# Z05_MB_01.net
KiCad netlist of a schematic drawn in EAGLE
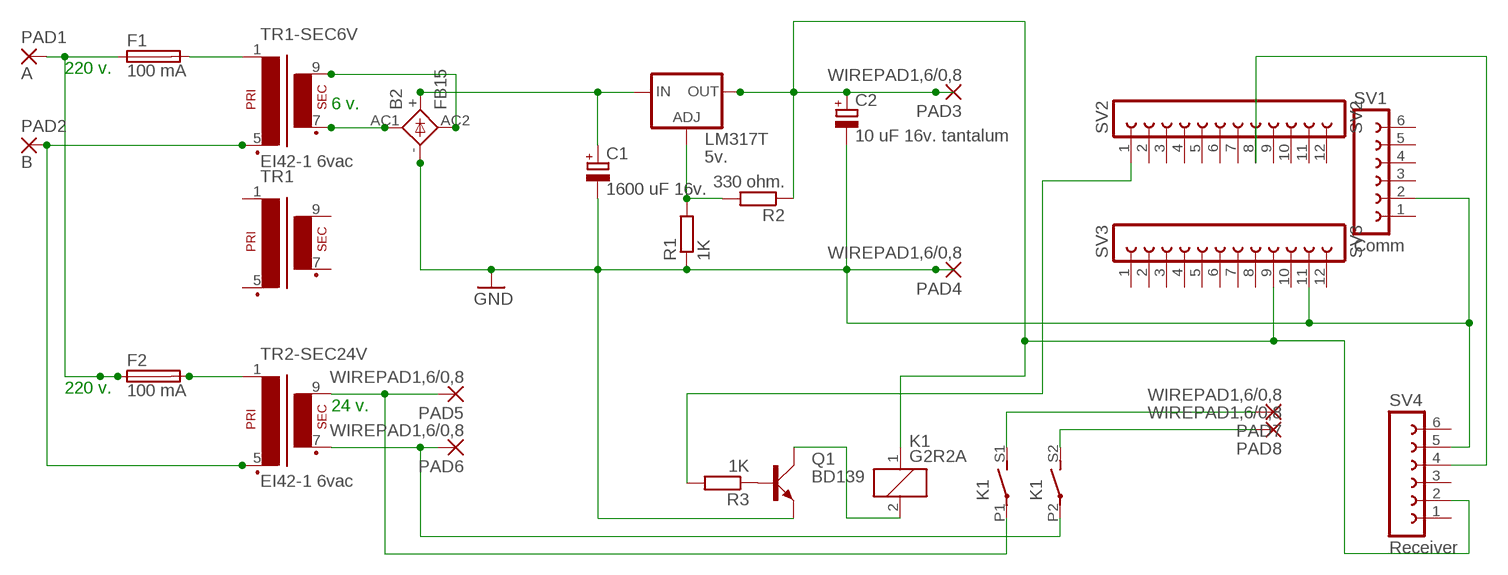
[diagram p0: schematic, sheet 1]

(export (version "E")
  (design (tool "Eeschema 10.0.6"))
  (components
    (comp (ref "B2")
      (value "FB15")
      (footprint "eagle-import:FB15")
      (libsource (lib "eagle-import") (part "FB15"))
    )
    (comp (ref "C1")
      (value "1600 uF 16v.")
      (footprint "eagle-import:E5-13")
      (libsource (lib "eagle-import") (part "CPOL-EUE5-13"))
    )
    (comp (ref "C2")
      (value "10 uF 16v. tantalum")
      (footprint "eagle-import:TAP5-60")
      (libsource (lib "eagle-import") (part "CPOL-EUTAP5-60"))
    )
    (comp (ref "F1")
      (value "100 mA")
      (footprint "eagle-import:GSH15")
      (fields (field (name "MPN") "64900001039"))
      (libsource (lib "eagle-import") (part "GSH15"))
    )
    (comp (ref "F2")
      (value "100 mA")
      (footprint "eagle-import:GSH15")
      (fields (field (name "MPN") "64900001039"))
      (libsource (lib "eagle-import") (part "GSH15"))
    )
    (comp (ref "K1")
      (value "G2R2A")
      (footprint "eagle-import:G2R2A")
      (fields (field (name "MPN") "G2R-2A-DC24"))
      (libsource (lib "eagle-import") (part "G2R2A"))
    )
    (comp (ref "LM317T")
      (value "5v.")
      (footprint "eagle-import:317TS")
      (libsource (lib "eagle-import") (part "LM317TS"))
    )
    (comp (ref "PAD1")
      (value "A")
      (footprint "eagle-import:2,54_1,1")
      (libsource (lib "eagle-import") (part "2,54/1,1"))
    )
    (comp (ref "PAD2")
      (value "B")
      (footprint "eagle-import:2,54_1,1")
      (libsource (lib "eagle-import") (part "2,54/1,1"))
    )
    (comp (ref "PAD3")
      (value "WIREPAD1,6/0,8")
      (footprint "eagle-import:1,6_0,8")
      (libsource (lib "eagle-import") (part "WIREPAD1,6/0,8"))
    )
    (comp (ref "PAD4")
      (value "WIREPAD1,6/0,8")
      (footprint "eagle-import:1,6_0,8")
      (libsource (lib "eagle-import") (part "WIREPAD1,6/0,8"))
    )
    (comp (ref "PAD5")
      (value "WIREPAD1,6/0,8")
      (footprint "eagle-import:1,6_0,8")
      (libsource (lib "eagle-import") (part "WIREPAD1,6/0,8"))
    )
    (comp (ref "PAD6")
      (value "WIREPAD1,6/0,8")
      (footprint "eagle-import:1,6_0,8")
      (libsource (lib "eagle-import") (part "WIREPAD1,6/0,8"))
    )
    (comp (ref "PAD7")
      (value "WIREPAD1,6/0,8")
      (footprint "eagle-import:1,6_0,8")
      (libsource (lib "eagle-import") (part "WIREPAD1,6/0,8"))
    )
    (comp (ref "PAD8")
      (value "WIREPAD1,6/0,8")
      (footprint "eagle-import:1,6_0,8")
      (libsource (lib "eagle-import") (part "WIREPAD1,6/0,8"))
    )
    (comp (ref "Q1")
      (value "BD139")
      (footprint "eagle-import:TO126AV")
      (libsource (lib "eagle-import") (part "BD139"))
    )
    (comp (ref "R1")
      (value "1K")
      (footprint "eagle-import:0207_12")
      (libsource (lib "eagle-import") (part "R-EU_0207/12"))
    )
    (comp (ref "R2")
      (value "330 ohm.")
      (footprint "eagle-import:0207_12")
      (libsource (lib "eagle-import") (part "R-EU_0207/12"))
    )
    (comp (ref "R3")
      (value "1K")
      (footprint "eagle-import:0207_12")
      (libsource (lib "eagle-import") (part "R-EU_0207/12"))
    )
    (comp (ref "SV1")
      (value "Comm")
      (footprint "eagle-import:FE06")
      (libsource (lib "eagle-import") (part "FE06-1"))
    )
    (comp (ref "SV2")
      (value "SV2")
      (footprint "eagle-import:FE12")
      (libsource (lib "eagle-import") (part "FE12-1"))
    )
    (comp (ref "SV3")
      (value "SV3")
      (footprint "eagle-import:FE12")
      (libsource (lib "eagle-import") (part "FE12-1"))
    )
    (comp (ref "SV4")
      (value "Receiver")
      (footprint "eagle-import:FE06")
      (fields (field (name "OC_FARNELL") "unknown") (field (name "OC_NEWARK") "unknown"))
      (libsource (lib "eagle-import") (part "FE06-1"))
    )
    (comp (ref "TR1")
      (value "EI30-1")
      (footprint "eagle-import:EI30-1")
      (libsource (lib "eagle-import") (part "EI30-1"))
    )
    (comp (ref "TR1-SEC6V")
      (value "EI42-1 6vac")
      (footprint "eagle-import:EI42-1")
      (libsource (lib "eagle-import") (part "EI42-1"))
    )
    (comp (ref "TR2-SEC24V")
      (value "EI42-1 6vac")
      (footprint "eagle-import:EI42-1")
      (libsource (lib "eagle-import") (part "EI42-1"))
    )
  )
  (nets
    (net (code "1") (name "GND") (class "Default")
      (node (ref "B2") (pin "-") (pinfunction "-_-") (pintype "passive"))
      (node (ref "C1") (pin "-") (pinfunction "-_-") (pintype "passive"))
      (node (ref "C2") (pin "-") (pinfunction "-_-") (pintype "passive"))
      (node (ref "PAD4") (pin "1") (pinfunction "P_1") (pintype "passive"))
      (node (ref "Q1") (pin "E") (pinfunction "E_E") (pintype "passive"))
      (node (ref "R1") (pin "1") (pinfunction "1_1") (pintype "passive"))
      (node (ref "SV1") (pin "2") (pinfunction "2_2") (pintype "passive"))
      (node (ref "SV3") (pin "11") (pinfunction "11_11") (pintype "passive"))
      (node (ref "SV4") (pin "5") (pinfunction "5_5") (pintype "passive"))
    )
    (net (code "2") (name "Net-(K1-Pad2)") (class "Default")
      (node (ref "K1") (pin "2") (pinfunction "2_2") (pintype "passive"))
      (node (ref "Q1") (pin "C") (pinfunction "C_C") (pintype "passive"))
    )
    (net (code "3") (name "Net-(K1B-P)") (class "Default")
      (node (ref "K1") (pin "P1") (pinfunction "P_P1") (pintype "passive"))
      (node (ref "PAD5") (pin "1") (pinfunction "P_1") (pintype "passive"))
      (node (ref "TR2-SEC24V") (pin "9") (pinfunction "S4_9") (pintype "passive"))
    )
    (net (code "4") (name "Net-(K1B-S)") (class "Default")
      (node (ref "K1") (pin "S1") (pinfunction "S_S1") (pintype "passive"))
      (node (ref "PAD7") (pin "1") (pinfunction "P_1") (pintype "passive"))
    )
    (net (code "5") (name "Net-(K1C-P)") (class "Default")
      (node (ref "K1") (pin "P2") (pinfunction "P_P2") (pintype "passive"))
      (node (ref "PAD6") (pin "1") (pinfunction "P_1") (pintype "passive"))
      (node (ref "TR2-SEC24V") (pin "7") (pinfunction "S3_7") (pintype "passive"))
    )
    (net (code "6") (name "Net-(K1C-S)") (class "Default")
      (node (ref "K1") (pin "S2") (pinfunction "S_S2") (pintype "passive"))
      (node (ref "PAD8") (pin "1") (pinfunction "P_1") (pintype "passive"))
    )
    (net (code "7") (name "Net-(LM317T-ADJ)") (class "Default")
      (node (ref "LM317T") (pin "1") (pinfunction "ADJ_1") (pintype "input"))
      (node (ref "R1") (pin "2") (pinfunction "2_2") (pintype "passive"))
      (node (ref "R2") (pin "2") (pinfunction "2_2") (pintype "passive"))
    )
    (net (code "8") (name "Net-(LM317T-IN)") (class "Default")
      (node (ref "B2") (pin "+") (pinfunction "+_+") (pintype "passive"))
      (node (ref "C1") (pin "+") (pinfunction "+_+") (pintype "passive"))
      (node (ref "LM317T") (pin "3") (pinfunction "IN_3") (pintype "input"))
    )
    (net (code "9") (name "Net-(LM317T-OUT)") (class "Default")
      (node (ref "C2") (pin "+") (pinfunction "+_+") (pintype "passive"))
      (node (ref "K1") (pin "1") (pinfunction "1_1") (pintype "passive"))
      (node (ref "LM317T") (pin "2") (pinfunction "OUT_2") (pintype "passive"))
      (node (ref "PAD3") (pin "1") (pinfunction "P_1") (pintype "passive"))
      (node (ref "R2") (pin "1") (pinfunction "1_1") (pintype "passive"))
      (node (ref "SV3") (pin "9") (pinfunction "9_9") (pintype "passive"))
      (node (ref "SV4") (pin "2") (pinfunction "2_2") (pintype "passive"))
    )
    (net (code "10") (name "Net-(PAD1-P)") (class "Default")
      (node (ref "F1") (pin "1") (pinfunction "1_1") (pintype "passive"))
      (node (ref "F2") (pin "1") (pinfunction "1_1") (pintype "passive"))
      (node (ref "PAD1") (pin "1") (pinfunction "P_1") (pintype "passive"))
    )
    (net (code "11") (name "Net-(PAD2-P)") (class "Default")
      (node (ref "PAD2") (pin "1") (pinfunction "P_1") (pintype "passive"))
      (node (ref "TR1-SEC6V") (pin "5") (pinfunction "P2_5") (pintype "passive"))
      (node (ref "TR2-SEC24V") (pin "5") (pinfunction "P2_5") (pintype "passive"))
    )
    (net (code "12") (name "Net-(Q1-PadB)") (class "Default")
      (node (ref "Q1") (pin "B") (pinfunction "B_B") (pintype "passive"))
      (node (ref "R3") (pin "1") (pinfunction "1_1") (pintype "passive"))
    )
    (net (code "13") (name "Net-(R3-Pad2)") (class "Default")
      (node (ref "R3") (pin "2") (pinfunction "2_2") (pintype "passive"))
      (node (ref "SV2") (pin "1") (pinfunction "1_1") (pintype "passive"))
    )
    (net (code "14") (name "Net-(SV2-Pad8)") (class "Default")
      (node (ref "SV2") (pin "8") (pinfunction "8_8") (pintype "passive"))
      (node (ref "SV4") (pin "4") (pinfunction "4_4") (pintype "passive"))
    )
    (net (code "15") (name "Net-(TR1-SEC6V-P1)") (class "Default")
      (node (ref "F1") (pin "2") (pinfunction "2_2") (pintype "passive"))
      (node (ref "TR1-SEC6V") (pin "1") (pinfunction "P1_1") (pintype "passive"))
    )
    (net (code "16") (name "Net-(TR1-SEC6V-S3)") (class "Default")
      (node (ref "B2") (pin "AC1") (pinfunction "AC1_AC1") (pintype "passive"))
      (node (ref "TR1-SEC6V") (pin "7") (pinfunction "S3_7") (pintype "passive"))
    )
    (net (code "17") (name "Net-(TR1-SEC6V-S4)") (class "Default")
      (node (ref "B2") (pin "AC2") (pinfunction "AC2_AC2") (pintype "passive"))
      (node (ref "TR1-SEC6V") (pin "9") (pinfunction "S4_9") (pintype "passive"))
    )
    (net (code "18") (name "Net-(TR2-SEC24V-P1)") (class "Default")
      (node (ref "F2") (pin "2") (pinfunction "2_2") (pintype "passive"))
      (node (ref "TR2-SEC24V") (pin "1") (pinfunction "P1_1") (pintype "passive"))
    )
    (net (code "19") (name "unconnected-(SV1-Pad1)") (class "Default")
      (node (ref "SV1") (pin "1") (pinfunction "1_1") (pintype "passive"))
    )
    (net (code "20") (name "unconnected-(SV1-Pad3)") (class "Default")
      (node (ref "SV1") (pin "3") (pinfunction "3_3") (pintype "passive"))
    )
    (net (code "21") (name "unconnected-(SV1-Pad4)") (class "Default")
      (node (ref "SV1") (pin "4") (pinfunction "4_4") (pintype "passive"))
    )
    (net (code "22") (name "unconnected-(SV1-Pad5)") (class "Default")
      (node (ref "SV1") (pin "5") (pinfunction "5_5") (pintype "passive"))
    )
    (net (code "23") (name "unconnected-(SV1-Pad6)") (class "Default")
      (node (ref "SV1") (pin "6") (pinfunction "6_6") (pintype "passive"))
    )
    (net (code "24") (name "unconnected-(SV2-Pad2)") (class "Default")
      (node (ref "SV2") (pin "2") (pinfunction "2_2") (pintype "passive"))
    )
    (net (code "25") (name "unconnected-(SV2-Pad3)") (class "Default")
      (node (ref "SV2") (pin "3") (pinfunction "3_3") (pintype "passive"))
    )
    (net (code "26") (name "unconnected-(SV2-Pad4)") (class "Default")
      (node (ref "SV2") (pin "4") (pinfunction "4_4") (pintype "passive"))
    )
    (net (code "27") (name "unconnected-(SV2-Pad5)") (class "Default")
      (node (ref "SV2") (pin "5") (pinfunction "5_5") (pintype "passive"))
    )
    (net (code "28") (name "unconnected-(SV2-Pad6)") (class "Default")
      (node (ref "SV2") (pin "6") (pinfunction "6_6") (pintype "passive"))
    )
    (net (code "29") (name "unconnected-(SV2-Pad7)") (class "Default")
      (node (ref "SV2") (pin "7") (pinfunction "7_7") (pintype "passive"))
    )
    (net (code "30") (name "unconnected-(SV2-Pad9)") (class "Default")
      (node (ref "SV2") (pin "9") (pinfunction "9_9") (pintype "passive"))
    )
    (net (code "31") (name "unconnected-(SV2-Pad10)") (class "Default")
      (node (ref "SV2") (pin "10") (pinfunction "10_10") (pintype "passive"))
    )
    (net (code "32") (name "unconnected-(SV2-Pad11)") (class "Default")
      (node (ref "SV2") (pin "11") (pinfunction "11_11") (pintype "passive"))
    )
    (net (code "33") (name "unconnected-(SV2-Pad12)") (class "Default")
      (node (ref "SV2") (pin "12") (pinfunction "12_12") (pintype "passive"))
    )
    (net (code "34") (name "unconnected-(SV3-Pad1)") (class "Default")
      (node (ref "SV3") (pin "1") (pinfunction "1_1") (pintype "passive"))
    )
    (net (code "35") (name "unconnected-(SV3-Pad2)") (class "Default")
      (node (ref "SV3") (pin "2") (pinfunction "2_2") (pintype "passive"))
    )
    (net (code "36") (name "unconnected-(SV3-Pad3)") (class "Default")
      (node (ref "SV3") (pin "3") (pinfunction "3_3") (pintype "passive"))
    )
    (net (code "37") (name "unconnected-(SV3-Pad4)") (class "Default")
      (node (ref "SV3") (pin "4") (pinfunction "4_4") (pintype "passive"))
    )
    (net (code "38") (name "unconnected-(SV3-Pad5)") (class "Default")
      (node (ref "SV3") (pin "5") (pinfunction "5_5") (pintype "passive"))
    )
    (net (code "39") (name "unconnected-(SV3-Pad6)") (class "Default")
      (node (ref "SV3") (pin "6") (pinfunction "6_6") (pintype "passive"))
    )
    (net (code "40") (name "unconnected-(SV3-Pad7)") (class "Default")
      (node (ref "SV3") (pin "7") (pinfunction "7_7") (pintype "passive"))
    )
    (net (code "41") (name "unconnected-(SV3-Pad8)") (class "Default")
      (node (ref "SV3") (pin "8") (pinfunction "8_8") (pintype "passive"))
    )
    (net (code "42") (name "unconnected-(SV3-Pad10)") (class "Default")
      (node (ref "SV3") (pin "10") (pinfunction "10_10") (pintype "passive"))
    )
    (net (code "43") (name "unconnected-(SV3-Pad12)") (class "Default")
      (node (ref "SV3") (pin "12") (pinfunction "12_12") (pintype "passive"))
    )
    (net (code "44") (name "unconnected-(SV4-Pad1)") (class "Default")
      (node (ref "SV4") (pin "1") (pinfunction "1_1") (pintype "passive"))
    )
    (net (code "45") (name "unconnected-(SV4-Pad3)") (class "Default")
      (node (ref "SV4") (pin "3") (pinfunction "3_3") (pintype "passive"))
    )
    (net (code "46") (name "unconnected-(SV4-Pad6)") (class "Default")
      (node (ref "SV4") (pin "6") (pinfunction "6_6") (pintype "passive"))
    )
    (net (code "47") (name "unconnected-(TR1-P1-Pad1)") (class "Default")
      (node (ref "TR1") (pin "1") (pinfunction "P1_1") (pintype "passive"))
    )
    (net (code "48") (name "unconnected-(TR1-P2-Pad5)") (class "Default")
      (node (ref "TR1") (pin "5") (pinfunction "P2_5") (pintype "passive"))
    )
    (net (code "49") (name "unconnected-(TR1-S3-Pad7)") (class "Default")
      (node (ref "TR1") (pin "7") (pinfunction "S3_7") (pintype "passive"))
    )
    (net (code "50") (name "unconnected-(TR1-S4-Pad9)") (class "Default")
      (node (ref "TR1") (pin "9") (pinfunction "S4_9") (pintype "passive"))
    )
  )
)
